# Ing_DC2013.net
KiCad netlist of a schematic drawn in EAGLE
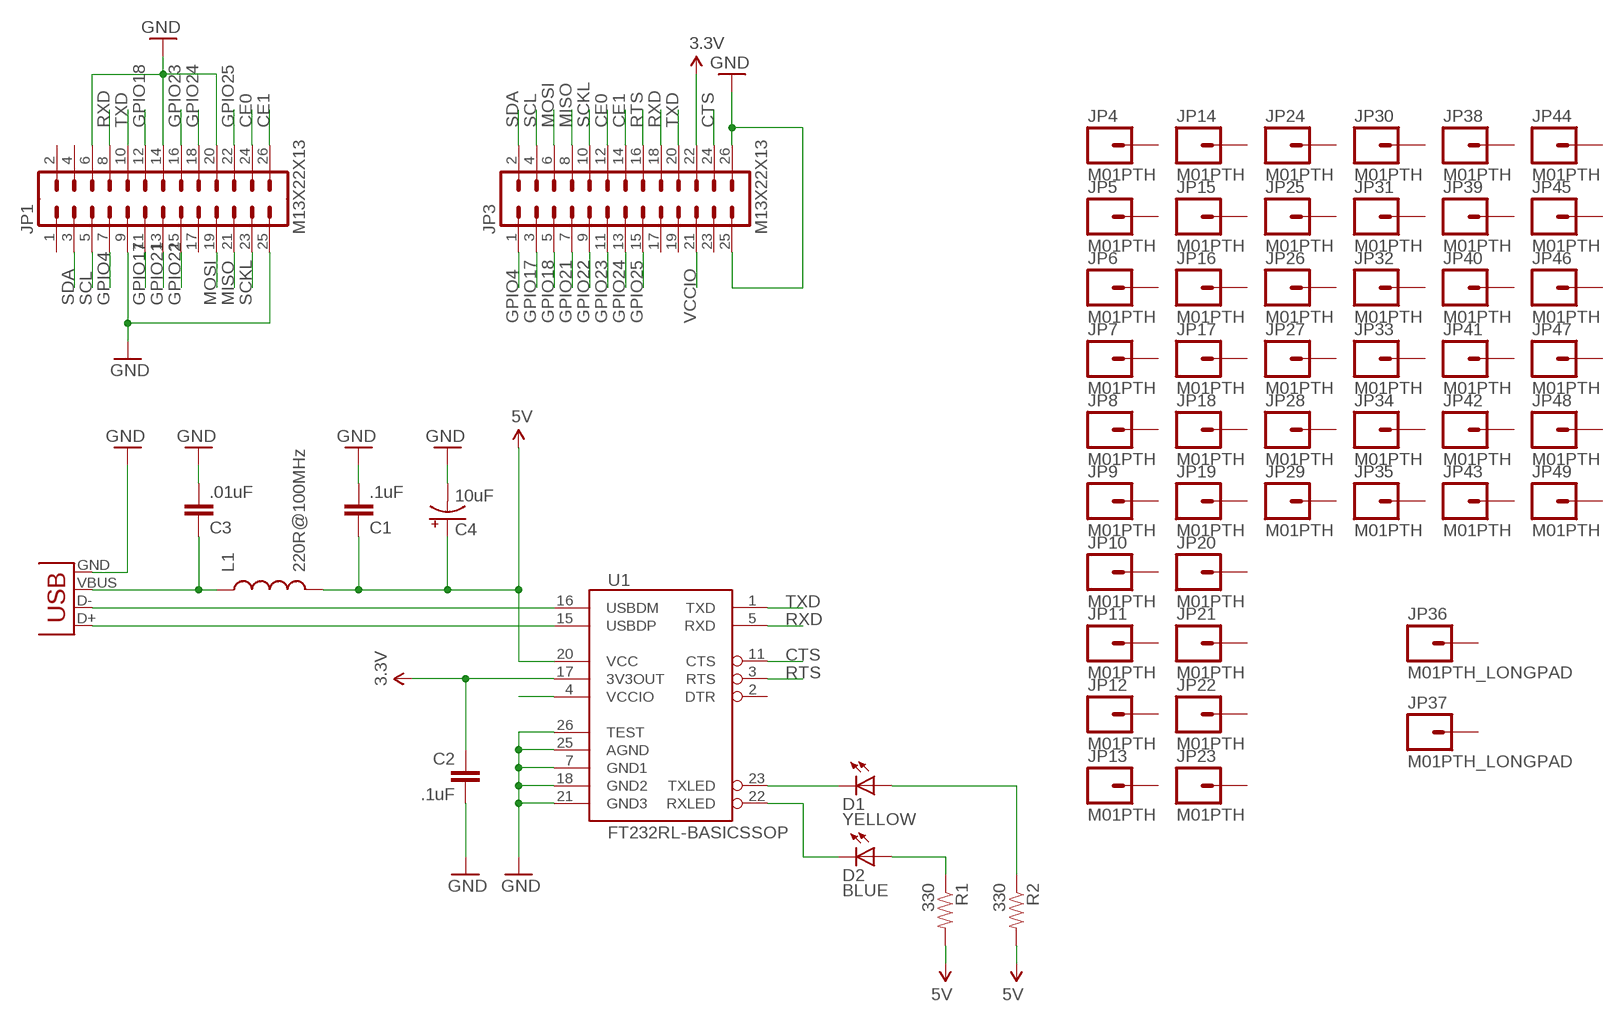
[diagram p0: schematic, sheet 1]

(export (version "E")
  (design (tool "Eeschema 10.0.6"))
  (components
    (comp (ref "C1")
      (value ".1uF")
      (footprint "eagle-import:1206")
      (libsource (lib "eagle-import") (part "CAP1206"))
    )
    (comp (ref "C2")
      (value ".1uF")
      (footprint "eagle-import:1206")
      (libsource (lib "eagle-import") (part "CAP1206"))
    )
    (comp (ref "C3")
      (value ".01uF")
      (footprint "eagle-import:1206")
      (libsource (lib "eagle-import") (part "CAP1206"))
    )
    (comp (ref "C4")
      (value "10uF")
      (footprint "eagle-import:EIA3216")
      (libsource (lib "eagle-import") (part "CAP_POL1206"))
    )
    (comp (ref "D1")
      (value "YELLOW")
      (footprint "eagle-import:LED-1206")
      (libsource (lib "eagle-import") (part "LED-RED1206"))
    )
    (comp (ref "D2")
      (value "BLUE")
      (footprint "eagle-import:LED-1206")
      (libsource (lib "eagle-import") (part "LED-GREENLARGE"))
    )
    (comp (ref "JP1")
      (value "M13X22X13")
      (footprint "eagle-import:2X13")
      (libsource (lib "eagle-import") (part "M13X22X13"))
    )
    (comp (ref "JP2")
      (value "USB-SMD-NS")
      (footprint "eagle-import:USB-MINIB-NOSTOP")
      (libsource (lib "eagle-import") (part "USB-SMD-NS"))
    )
    (comp (ref "JP3")
      (value "M13X22X13")
      (footprint "eagle-import:2X13")
      (libsource (lib "eagle-import") (part "M13X22X13"))
    )
    (comp (ref "JP4")
      (value "M01PTH")
      (footprint "eagle-import:1X01")
      (libsource (lib "eagle-import") (part "M01PTH"))
    )
    (comp (ref "JP5")
      (value "M01PTH")
      (footprint "eagle-import:1X01")
      (libsource (lib "eagle-import") (part "M01PTH"))
    )
    (comp (ref "JP6")
      (value "M01PTH")
      (footprint "eagle-import:1X01")
      (libsource (lib "eagle-import") (part "M01PTH"))
    )
    (comp (ref "JP7")
      (value "M01PTH")
      (footprint "eagle-import:1X01")
      (libsource (lib "eagle-import") (part "M01PTH"))
    )
    (comp (ref "JP8")
      (value "M01PTH")
      (footprint "eagle-import:1X01")
      (libsource (lib "eagle-import") (part "M01PTH"))
    )
    (comp (ref "JP9")
      (value "M01PTH")
      (footprint "eagle-import:1X01")
      (libsource (lib "eagle-import") (part "M01PTH"))
    )
    (comp (ref "JP10")
      (value "M01PTH")
      (footprint "eagle-import:1X01")
      (libsource (lib "eagle-import") (part "M01PTH"))
    )
    (comp (ref "JP11")
      (value "M01PTH")
      (footprint "eagle-import:1X01")
      (libsource (lib "eagle-import") (part "M01PTH"))
    )
    (comp (ref "JP12")
      (value "M01PTH")
      (footprint "eagle-import:1X01")
      (libsource (lib "eagle-import") (part "M01PTH"))
    )
    (comp (ref "JP13")
      (value "M01PTH")
      (footprint "eagle-import:1X01")
      (libsource (lib "eagle-import") (part "M01PTH"))
    )
    (comp (ref "JP14")
      (value "M01PTH")
      (footprint "eagle-import:1X01")
      (libsource (lib "eagle-import") (part "M01PTH"))
    )
    (comp (ref "JP15")
      (value "M01PTH")
      (footprint "eagle-import:1X01")
      (libsource (lib "eagle-import") (part "M01PTH"))
    )
    (comp (ref "JP16")
      (value "M01PTH")
      (footprint "eagle-import:1X01")
      (libsource (lib "eagle-import") (part "M01PTH"))
    )
    (comp (ref "JP17")
      (value "M01PTH")
      (footprint "eagle-import:1X01")
      (libsource (lib "eagle-import") (part "M01PTH"))
    )
    (comp (ref "JP18")
      (value "M01PTH")
      (footprint "eagle-import:1X01")
      (libsource (lib "eagle-import") (part "M01PTH"))
    )
    (comp (ref "JP19")
      (value "M01PTH")
      (footprint "eagle-import:1X01")
      (libsource (lib "eagle-import") (part "M01PTH"))
    )
    (comp (ref "JP20")
      (value "M01PTH")
      (footprint "eagle-import:1X01")
      (libsource (lib "eagle-import") (part "M01PTH"))
    )
    (comp (ref "JP21")
      (value "M01PTH")
      (footprint "eagle-import:1X01")
      (libsource (lib "eagle-import") (part "M01PTH"))
    )
    (comp (ref "JP22")
      (value "M01PTH")
      (footprint "eagle-import:1X01")
      (libsource (lib "eagle-import") (part "M01PTH"))
    )
    (comp (ref "JP23")
      (value "M01PTH")
      (footprint "eagle-import:1X01")
      (libsource (lib "eagle-import") (part "M01PTH"))
    )
    (comp (ref "JP24")
      (value "M01PTH")
      (footprint "eagle-import:1X01")
      (libsource (lib "eagle-import") (part "M01PTH"))
    )
    (comp (ref "JP25")
      (value "M01PTH")
      (footprint "eagle-import:1X01")
      (libsource (lib "eagle-import") (part "M01PTH"))
    )
    (comp (ref "JP26")
      (value "M01PTH")
      (footprint "eagle-import:1X01")
      (libsource (lib "eagle-import") (part "M01PTH"))
    )
    (comp (ref "JP27")
      (value "M01PTH")
      (footprint "eagle-import:1X01")
      (libsource (lib "eagle-import") (part "M01PTH"))
    )
    (comp (ref "JP28")
      (value "M01PTH")
      (footprint "eagle-import:1X01")
      (libsource (lib "eagle-import") (part "M01PTH"))
    )
    (comp (ref "JP29")
      (value "M01PTH")
      (footprint "eagle-import:1X01")
      (libsource (lib "eagle-import") (part "M01PTH"))
    )
    (comp (ref "JP30")
      (value "M01PTH")
      (footprint "eagle-import:1X01")
      (libsource (lib "eagle-import") (part "M01PTH"))
    )
    (comp (ref "JP31")
      (value "M01PTH")
      (footprint "eagle-import:1X01")
      (libsource (lib "eagle-import") (part "M01PTH"))
    )
    (comp (ref "JP32")
      (value "M01PTH")
      (footprint "eagle-import:1X01")
      (libsource (lib "eagle-import") (part "M01PTH"))
    )
    (comp (ref "JP33")
      (value "M01PTH")
      (footprint "eagle-import:1X01")
      (libsource (lib "eagle-import") (part "M01PTH"))
    )
    (comp (ref "JP34")
      (value "M01PTH")
      (footprint "eagle-import:1X01")
      (libsource (lib "eagle-import") (part "M01PTH"))
    )
    (comp (ref "JP35")
      (value "M01PTH")
      (footprint "eagle-import:1X01")
      (libsource (lib "eagle-import") (part "M01PTH"))
    )
    (comp (ref "JP36")
      (value "M01PTH_LONGPAD")
      (footprint "eagle-import:1X01_LONGPAD")
      (libsource (lib "eagle-import") (part "M01PTH_LONGPAD"))
    )
    (comp (ref "JP37")
      (value "M01PTH_LONGPAD")
      (footprint "eagle-import:1X01_LONGPAD")
      (libsource (lib "eagle-import") (part "M01PTH_LONGPAD"))
    )
    (comp (ref "JP38")
      (value "M01PTH")
      (footprint "eagle-import:1X01")
      (libsource (lib "eagle-import") (part "M01PTH"))
    )
    (comp (ref "JP39")
      (value "M01PTH")
      (footprint "eagle-import:1X01")
      (libsource (lib "eagle-import") (part "M01PTH"))
    )
    (comp (ref "JP40")
      (value "M01PTH")
      (footprint "eagle-import:1X01")
      (libsource (lib "eagle-import") (part "M01PTH"))
    )
    (comp (ref "JP41")
      (value "M01PTH")
      (footprint "eagle-import:1X01")
      (libsource (lib "eagle-import") (part "M01PTH"))
    )
    (comp (ref "JP42")
      (value "M01PTH")
      (footprint "eagle-import:1X01")
      (libsource (lib "eagle-import") (part "M01PTH"))
    )
    (comp (ref "JP43")
      (value "M01PTH")
      (footprint "eagle-import:1X01")
      (libsource (lib "eagle-import") (part "M01PTH"))
    )
    (comp (ref "JP44")
      (value "M01PTH")
      (footprint "eagle-import:1X01")
      (libsource (lib "eagle-import") (part "M01PTH"))
    )
    (comp (ref "JP45")
      (value "M01PTH")
      (footprint "eagle-import:1X01")
      (libsource (lib "eagle-import") (part "M01PTH"))
    )
    (comp (ref "JP46")
      (value "M01PTH")
      (footprint "eagle-import:1X01")
      (libsource (lib "eagle-import") (part "M01PTH"))
    )
    (comp (ref "JP47")
      (value "M01PTH")
      (footprint "eagle-import:1X01")
      (libsource (lib "eagle-import") (part "M01PTH"))
    )
    (comp (ref "JP48")
      (value "M01PTH")
      (footprint "eagle-import:1X01")
      (libsource (lib "eagle-import") (part "M01PTH"))
    )
    (comp (ref "JP49")
      (value "M01PTH")
      (footprint "eagle-import:1X01")
      (libsource (lib "eagle-import") (part "M01PTH"))
    )
    (comp (ref "L1")
      (value "220R@100MHz")
      (footprint "eagle-import:1210")
      (libsource (lib "eagle-import") (part "INDUCTOR1210"))
    )
    (comp (ref "R1")
      (value "330")
      (footprint "eagle-import:1206")
      (libsource (lib "eagle-import") (part "RESISTOR1206"))
    )
    (comp (ref "R2")
      (value "330")
      (footprint "eagle-import:1206")
      (libsource (lib "eagle-import") (part "RESISTOR1206"))
    )
    (comp (ref "U1")
      (value "FT232RL-BASICSSOP")
      (footprint "eagle-import:SSOP28DB")
      (libsource (lib "eagle-import") (part "FT232RL-BASICSSOP"))
    )
  )
  (nets
    (net (code "1") (name "/CE0") (class "Default")
      (node (ref "JP1") (pin "24") (pinfunction "24_24") (pintype "passive"))
      (node (ref "JP3") (pin "12") (pinfunction "12_12") (pintype "passive"))
    )
    (net (code "2") (name "/CE1") (class "Default")
      (node (ref "JP1") (pin "26") (pinfunction "26_26") (pintype "passive"))
      (node (ref "JP3") (pin "14") (pinfunction "14_14") (pintype "passive"))
    )
    (net (code "3") (name "/CTS") (class "Default")
      (node (ref "JP3") (pin "24") (pinfunction "24_24") (pintype "passive"))
      (node (ref "U1") (pin "11") (pinfunction "CTS_11") (pintype "bidirectional"))
    )
    (net (code "4") (name "/GPIO4") (class "Default")
      (node (ref "JP1") (pin "7") (pinfunction "7_7") (pintype "passive"))
      (node (ref "JP3") (pin "1") (pinfunction "1_1") (pintype "passive"))
    )
    (net (code "5") (name "/GPIO17") (class "Default")
      (node (ref "JP1") (pin "11") (pinfunction "11_11") (pintype "passive"))
      (node (ref "JP3") (pin "3") (pinfunction "3_3") (pintype "passive"))
    )
    (net (code "6") (name "/GPIO18") (class "Default")
      (node (ref "JP1") (pin "12") (pinfunction "12_12") (pintype "passive"))
      (node (ref "JP3") (pin "5") (pinfunction "5_5") (pintype "passive"))
    )
    (net (code "7") (name "/GPIO21") (class "Default")
      (node (ref "JP1") (pin "13") (pinfunction "13_13") (pintype "passive"))
      (node (ref "JP3") (pin "7") (pinfunction "7_7") (pintype "passive"))
    )
    (net (code "8") (name "/GPIO22") (class "Default")
      (node (ref "JP1") (pin "15") (pinfunction "15_15") (pintype "passive"))
      (node (ref "JP3") (pin "9") (pinfunction "9_9") (pintype "passive"))
    )
    (net (code "9") (name "/GPIO23") (class "Default")
      (node (ref "JP1") (pin "16") (pinfunction "16_16") (pintype "passive"))
      (node (ref "JP3") (pin "11") (pinfunction "11_11") (pintype "passive"))
    )
    (net (code "10") (name "/GPIO24") (class "Default")
      (node (ref "JP1") (pin "18") (pinfunction "18_18") (pintype "passive"))
      (node (ref "JP3") (pin "13") (pinfunction "13_13") (pintype "passive"))
    )
    (net (code "11") (name "/GPIO25") (class "Default")
      (node (ref "JP1") (pin "22") (pinfunction "22_22") (pintype "passive"))
      (node (ref "JP3") (pin "15") (pinfunction "15_15") (pintype "passive"))
    )
    (net (code "12") (name "/MISO") (class "Default")
      (node (ref "JP1") (pin "21") (pinfunction "21_21") (pintype "passive"))
      (node (ref "JP3") (pin "8") (pinfunction "8_8") (pintype "passive"))
    )
    (net (code "13") (name "/MOSI") (class "Default")
      (node (ref "JP1") (pin "19") (pinfunction "19_19") (pintype "passive"))
      (node (ref "JP3") (pin "6") (pinfunction "6_6") (pintype "passive"))
    )
    (net (code "14") (name "/RTS") (class "Default")
      (node (ref "JP3") (pin "16") (pinfunction "16_16") (pintype "passive"))
      (node (ref "U1") (pin "3") (pinfunction "RTS_3") (pintype "bidirectional"))
    )
    (net (code "15") (name "/RXD") (class "Default")
      (node (ref "JP1") (pin "8") (pinfunction "8_8") (pintype "passive"))
      (node (ref "JP3") (pin "18") (pinfunction "18_18") (pintype "passive"))
      (node (ref "U1") (pin "5") (pinfunction "RXD_5") (pintype "input"))
    )
    (net (code "16") (name "/SCKL") (class "Default")
      (node (ref "JP1") (pin "23") (pinfunction "23_23") (pintype "passive"))
      (node (ref "JP3") (pin "10") (pinfunction "10_10") (pintype "passive"))
    )
    (net (code "17") (name "/SCL") (class "Default")
      (node (ref "JP1") (pin "5") (pinfunction "5_5") (pintype "passive"))
      (node (ref "JP3") (pin "4") (pinfunction "4_4") (pintype "passive"))
    )
    (net (code "18") (name "/SDA") (class "Default")
      (node (ref "JP1") (pin "3") (pinfunction "3_3") (pintype "passive"))
      (node (ref "JP3") (pin "2") (pinfunction "2_2") (pintype "passive"))
    )
    (net (code "19") (name "/TXD") (class "Default")
      (node (ref "JP1") (pin "10") (pinfunction "10_10") (pintype "passive"))
      (node (ref "JP3") (pin "20") (pinfunction "20_20") (pintype "passive"))
      (node (ref "U1") (pin "1") (pinfunction "TXD_1") (pintype "output"))
    )
    (net (code "20") (name "/VCCIO") (class "Default")
      (node (ref "JP3") (pin "21") (pinfunction "21_21") (pintype "passive"))
      (node (ref "U1") (pin "4") (pinfunction "VCCIO_4") (pintype "power_in"))
    )
    (net (code "21") (name "3.3V") (class "Default")
      (node (ref "C2") (pin "1") (pinfunction "1_1") (pintype "passive"))
      (node (ref "JP3") (pin "22") (pinfunction "22_22") (pintype "passive"))
      (node (ref "U1") (pin "17") (pinfunction "3V3OUT_17") (pintype "output"))
    )
    (net (code "22") (name "5V") (class "Default")
      (node (ref "C1") (pin "1") (pinfunction "1_1") (pintype "passive"))
      (node (ref "C4") (pin "A") (pinfunction "+_A") (pintype "passive"))
      (node (ref "L1") (pin "2") (pinfunction "2_2") (pintype "passive"))
      (node (ref "R1") (pin "2") (pinfunction "2_2") (pintype "passive"))
      (node (ref "R2") (pin "2") (pinfunction "2_2") (pintype "passive"))
      (node (ref "U1") (pin "20") (pinfunction "VCC_20") (pintype "power_in"))
    )
    (net (code "23") (name "GND") (class "Default")
      (node (ref "C1") (pin "2") (pinfunction "2_2") (pintype "passive"))
      (node (ref "C2") (pin "2") (pinfunction "2_2") (pintype "passive"))
      (node (ref "C3") (pin "2") (pinfunction "2_2") (pintype "passive"))
      (node (ref "C4") (pin "C") (pinfunction "-_C") (pintype "passive"))
      (node (ref "JP1") (pin "14") (pinfunction "14_14") (pintype "passive"))
      (node (ref "JP1") (pin "20") (pinfunction "20_20") (pintype "passive"))
      (node (ref "JP1") (pin "25") (pinfunction "25_25") (pintype "passive"))
      (node (ref "JP1") (pin "6") (pinfunction "6_6") (pintype "passive"))
      (node (ref "JP1") (pin "9") (pinfunction "9_9") (pintype "passive"))
      (node (ref "JP2") (pin "GND") (pinfunction "GND_GND") (pintype "bidirectional"))
      (node (ref "JP3") (pin "25") (pinfunction "25_25") (pintype "passive"))
      (node (ref "JP3") (pin "26") (pinfunction "26_26") (pintype "passive"))
      (node (ref "U1") (pin "18") (pinfunction "GND2_18") (pintype "power_in"))
      (node (ref "U1") (pin "21") (pinfunction "GND3_21") (pintype "power_in"))
      (node (ref "U1") (pin "25") (pinfunction "AGND_25") (pintype "power_in"))
      (node (ref "U1") (pin "26") (pinfunction "TEST_26") (pintype "input"))
      (node (ref "U1") (pin "7") (pinfunction "GND1_7") (pintype "power_in"))
    )
    (net (code "24") (name "Net-(C3-Pad1)") (class "Default")
      (node (ref "C3") (pin "1") (pinfunction "1_1") (pintype "passive"))
      (node (ref "JP2") (pin "VBUS") (pinfunction "VBUS_VBUS") (pintype "bidirectional"))
      (node (ref "L1") (pin "1") (pinfunction "1_1") (pintype "passive"))
    )
    (net (code "25") (name "Net-(D1-PadA)") (class "Default")
      (node (ref "D1") (pin "A") (pinfunction "A_A") (pintype "passive"))
      (node (ref "R2") (pin "1") (pinfunction "1_1") (pintype "passive"))
    )
    (net (code "26") (name "Net-(D2-PadA)") (class "Default")
      (node (ref "D2") (pin "A") (pinfunction "A_A") (pintype "passive"))
      (node (ref "R1") (pin "1") (pinfunction "1_1") (pintype "passive"))
    )
    (net (code "27") (name "Net-(U1-RXLED)") (class "Default")
      (node (ref "D2") (pin "C") (pinfunction "C_C") (pintype "passive"))
      (node (ref "U1") (pin "22") (pinfunction "RXLED_22") (pintype "bidirectional"))
    )
    (net (code "28") (name "Net-(U1-TXLED)") (class "Default")
      (node (ref "D1") (pin "C") (pinfunction "C_C") (pintype "passive"))
      (node (ref "U1") (pin "23") (pinfunction "TXLED_23") (pintype "bidirectional"))
    )
    (net (code "29") (name "Net-(U1-USBDM)") (class "Default")
      (node (ref "JP2") (pin "D-") (pinfunction "D-_D-") (pintype "bidirectional"))
      (node (ref "U1") (pin "16") (pinfunction "USBDM_16") (pintype "bidirectional"))
    )
    (net (code "30") (name "Net-(U1-USBDP)") (class "Default")
      (node (ref "JP2") (pin "D+") (pinfunction "D+_D+") (pintype "bidirectional"))
      (node (ref "U1") (pin "15") (pinfunction "USBDP_15") (pintype "bidirectional"))
    )
    (net (code "31") (name "unconnected-(JP1-Pad1)") (class "Default")
      (node (ref "JP1") (pin "1") (pinfunction "1_1") (pintype "passive"))
    )
    (net (code "32") (name "unconnected-(JP1-Pad2)") (class "Default")
      (node (ref "JP1") (pin "2") (pinfunction "2_2") (pintype "passive"))
    )
    (net (code "33") (name "unconnected-(JP1-Pad4)") (class "Default")
      (node (ref "JP1") (pin "4") (pinfunction "4_4") (pintype "passive"))
    )
    (net (code "34") (name "unconnected-(JP1-Pad17)") (class "Default")
      (node (ref "JP1") (pin "17") (pinfunction "17_17") (pintype "passive"))
    )
    (net (code "35") (name "unconnected-(JP3-Pad17)") (class "Default")
      (node (ref "JP3") (pin "17") (pinfunction "17_17") (pintype "passive"))
    )
    (net (code "36") (name "unconnected-(JP3-Pad19)") (class "Default")
      (node (ref "JP3") (pin "19") (pinfunction "19_19") (pintype "passive"))
    )
    (net (code "37") (name "unconnected-(JP3-Pad23)") (class "Default")
      (node (ref "JP3") (pin "23") (pinfunction "23_23") (pintype "passive"))
    )
    (net (code "38") (name "unconnected-(JP4-Pad1)") (class "Default")
      (node (ref "JP4") (pin "1") (pinfunction "1_1") (pintype "passive"))
    )
    (net (code "39") (name "unconnected-(JP5-Pad1)") (class "Default")
      (node (ref "JP5") (pin "1") (pinfunction "1_1") (pintype "passive"))
    )
    (net (code "40") (name "unconnected-(JP6-Pad1)") (class "Default")
      (node (ref "JP6") (pin "1") (pinfunction "1_1") (pintype "passive"))
    )
    (net (code "41") (name "unconnected-(JP7-Pad1)") (class "Default")
      (node (ref "JP7") (pin "1") (pinfunction "1_1") (pintype "passive"))
    )
    (net (code "42") (name "unconnected-(JP8-Pad1)") (class "Default")
      (node (ref "JP8") (pin "1") (pinfunction "1_1") (pintype "passive"))
    )
    (net (code "43") (name "unconnected-(JP9-Pad1)") (class "Default")
      (node (ref "JP9") (pin "1") (pinfunction "1_1") (pintype "passive"))
    )
    (net (code "44") (name "unconnected-(JP10-Pad1)") (class "Default")
      (node (ref "JP10") (pin "1") (pinfunction "1_1") (pintype "passive"))
    )
    (net (code "45") (name "unconnected-(JP11-Pad1)") (class "Default")
      (node (ref "JP11") (pin "1") (pinfunction "1_1") (pintype "passive"))
    )
    (net (code "46") (name "unconnected-(JP12-Pad1)") (class "Default")
      (node (ref "JP12") (pin "1") (pinfunction "1_1") (pintype "passive"))
    )
    (net (code "47") (name "unconnected-(JP13-Pad1)") (class "Default")
      (node (ref "JP13") (pin "1") (pinfunction "1_1") (pintype "passive"))
    )
    (net (code "48") (name "unconnected-(JP14-Pad1)") (class "Default")
      (node (ref "JP14") (pin "1") (pinfunction "1_1") (pintype "passive"))
    )
    (net (code "49") (name "unconnected-(JP15-Pad1)") (class "Default")
      (node (ref "JP15") (pin "1") (pinfunction "1_1") (pintype "passive"))
    )
    (net (code "50") (name "unconnected-(JP16-Pad1)") (class "Default")
      (node (ref "JP16") (pin "1") (pinfunction "1_1") (pintype "passive"))
    )
    (net (code "51") (name "unconnected-(JP17-Pad1)") (class "Default")
      (node (ref "JP17") (pin "1") (pinfunction "1_1") (pintype "passive"))
    )
    (net (code "52") (name "unconnected-(JP18-Pad1)") (class "Default")
      (node (ref "JP18") (pin "1") (pinfunction "1_1") (pintype "passive"))
    )
    (net (code "53") (name "unconnected-(JP19-Pad1)") (class "Default")
      (node (ref "JP19") (pin "1") (pinfunction "1_1") (pintype "passive"))
    )
    (net (code "54") (name "unconnected-(JP20-Pad1)") (class "Default")
      (node (ref "JP20") (pin "1") (pinfunction "1_1") (pintype "passive"))
    )
    (net (code "55") (name "unconnected-(JP21-Pad1)") (class "Default")
      (node (ref "JP21") (pin "1") (pinfunction "1_1") (pintype "passive"))
    )
    (net (code "56") (name "unconnected-(JP22-Pad1)") (class "Default")
      (node (ref "JP22") (pin "1") (pinfunction "1_1") (pintype "passive"))
    )
    (net (code "57") (name "unconnected-(JP23-Pad1)") (class "Default")
      (node (ref "JP23") (pin "1") (pinfunction "1_1") (pintype "passive"))
    )
    (net (code "58") (name "unconnected-(JP24-Pad1)") (class "Default")
      (node (ref "JP24") (pin "1") (pinfunction "1_1") (pintype "passive"))
    )
    (net (code "59") (name "unconnected-(JP25-Pad1)") (class "Default")
      (node (ref "JP25") (pin "1") (pinfunction "1_1") (pintype "passive"))
    )
    (net (code "60") (name "unconnected-(JP26-Pad1)") (class "Default")
      (node (ref "JP26") (pin "1") (pinfunction "1_1") (pintype "passive"))
    )
    (net (code "61") (name "unconnected-(JP27-Pad1)") (class "Default")
      (node (ref "JP27") (pin "1") (pinfunction "1_1") (pintype "passive"))
    )
    (net (code "62") (name "unconnected-(JP28-Pad1)") (class "Default")
      (node (ref "JP28") (pin "1") (pinfunction "1_1") (pintype "passive"))
    )
    (net (code "63") (name "unconnected-(JP29-Pad1)") (class "Default")
      (node (ref "JP29") (pin "1") (pinfunction "1_1") (pintype "passive"))
    )
    (net (code "64") (name "unconnected-(JP30-Pad1)") (class "Default")
      (node (ref "JP30") (pin "1") (pinfunction "1_1") (pintype "passive"))
    )
    (net (code "65") (name "unconnected-(JP31-Pad1)") (class "Default")
      (node (ref "JP31") (pin "1") (pinfunction "1_1") (pintype "passive"))
    )
    (net (code "66") (name "unconnected-(JP32-Pad1)") (class "Default")
      (node (ref "JP32") (pin "1") (pinfunction "1_1") (pintype "passive"))
    )
    (net (code "67") (name "unconnected-(JP33-Pad1)") (class "Default")
      (node (ref "JP33") (pin "1") (pinfunction "1_1") (pintype "passive"))
    )
    (net (code "68") (name "unconnected-(JP34-Pad1)") (class "Default")
      (node (ref "JP34") (pin "1") (pinfunction "1_1") (pintype "passive"))
    )
    (net (code "69") (name "unconnected-(JP35-Pad1)") (class "Default")
      (node (ref "JP35") (pin "1") (pinfunction "1_1") (pintype "passive"))
    )
    (net (code "70") (name "unconnected-(JP36-Pad1)") (class "Default")
      (node (ref "JP36") (pin "1") (pinfunction "1_1") (pintype "passive"))
    )
    (net (code "71") (name "unconnected-(JP37-Pad1)") (class "Default")
      (node (ref "JP37") (pin "1") (pinfunction "1_1") (pintype "passive"))
    )
    (net (code "72") (name "unconnected-(JP38-Pad1)") (class "Default")
      (node (ref "JP38") (pin "1") (pinfunction "1_1") (pintype "passive"))
    )
    (net (code "73") (name "unconnected-(JP39-Pad1)") (class "Default")
      (node (ref "JP39") (pin "1") (pinfunction "1_1") (pintype "passive"))
    )
    (net (code "74") (name "unconnected-(JP40-Pad1)") (class "Default")
      (node (ref "JP40") (pin "1") (pinfunction "1_1") (pintype "passive"))
    )
    (net (code "75") (name "unconnected-(JP41-Pad1)") (class "Default")
      (node (ref "JP41") (pin "1") (pinfunction "1_1") (pintype "passive"))
    )
    (net (code "76") (name "unconnected-(JP42-Pad1)") (class "Default")
      (node (ref "JP42") (pin "1") (pinfunction "1_1") (pintype "passive"))
    )
    (net (code "77") (name "unconnected-(JP43-Pad1)") (class "Default")
      (node (ref "JP43") (pin "1") (pinfunction "1_1") (pintype "passive"))
    )
    (net (code "78") (name "unconnected-(JP44-Pad1)") (class "Default")
      (node (ref "JP44") (pin "1") (pinfunction "1_1") (pintype "passive"))
    )
    (net (code "79") (name "unconnected-(JP45-Pad1)") (class "Default")
      (node (ref "JP45") (pin "1") (pinfunction "1_1") (pintype "passive"))
    )
    (net (code "80") (name "unconnected-(JP46-Pad1)") (class "Default")
      (node (ref "JP46") (pin "1") (pinfunction "1_1") (pintype "passive"))
    )
    (net (code "81") (name "unconnected-(JP47-Pad1)") (class "Default")
      (node (ref "JP47") (pin "1") (pinfunction "1_1") (pintype "passive"))
    )
    (net (code "82") (name "unconnected-(JP48-Pad1)") (class "Default")
      (node (ref "JP48") (pin "1") (pinfunction "1_1") (pintype "passive"))
    )
    (net (code "83") (name "unconnected-(JP49-Pad1)") (class "Default")
      (node (ref "JP49") (pin "1") (pinfunction "1_1") (pintype "passive"))
    )
    (net (code "84") (name "unconnected-(U1-DTR-Pad2)") (class "Default")
      (node (ref "U1") (pin "2") (pinfunction "DTR_2") (pintype "bidirectional"))
    )
  )
)
